# Sheet1.net
KiCad netlist of a schematic drawn in Altium Designer
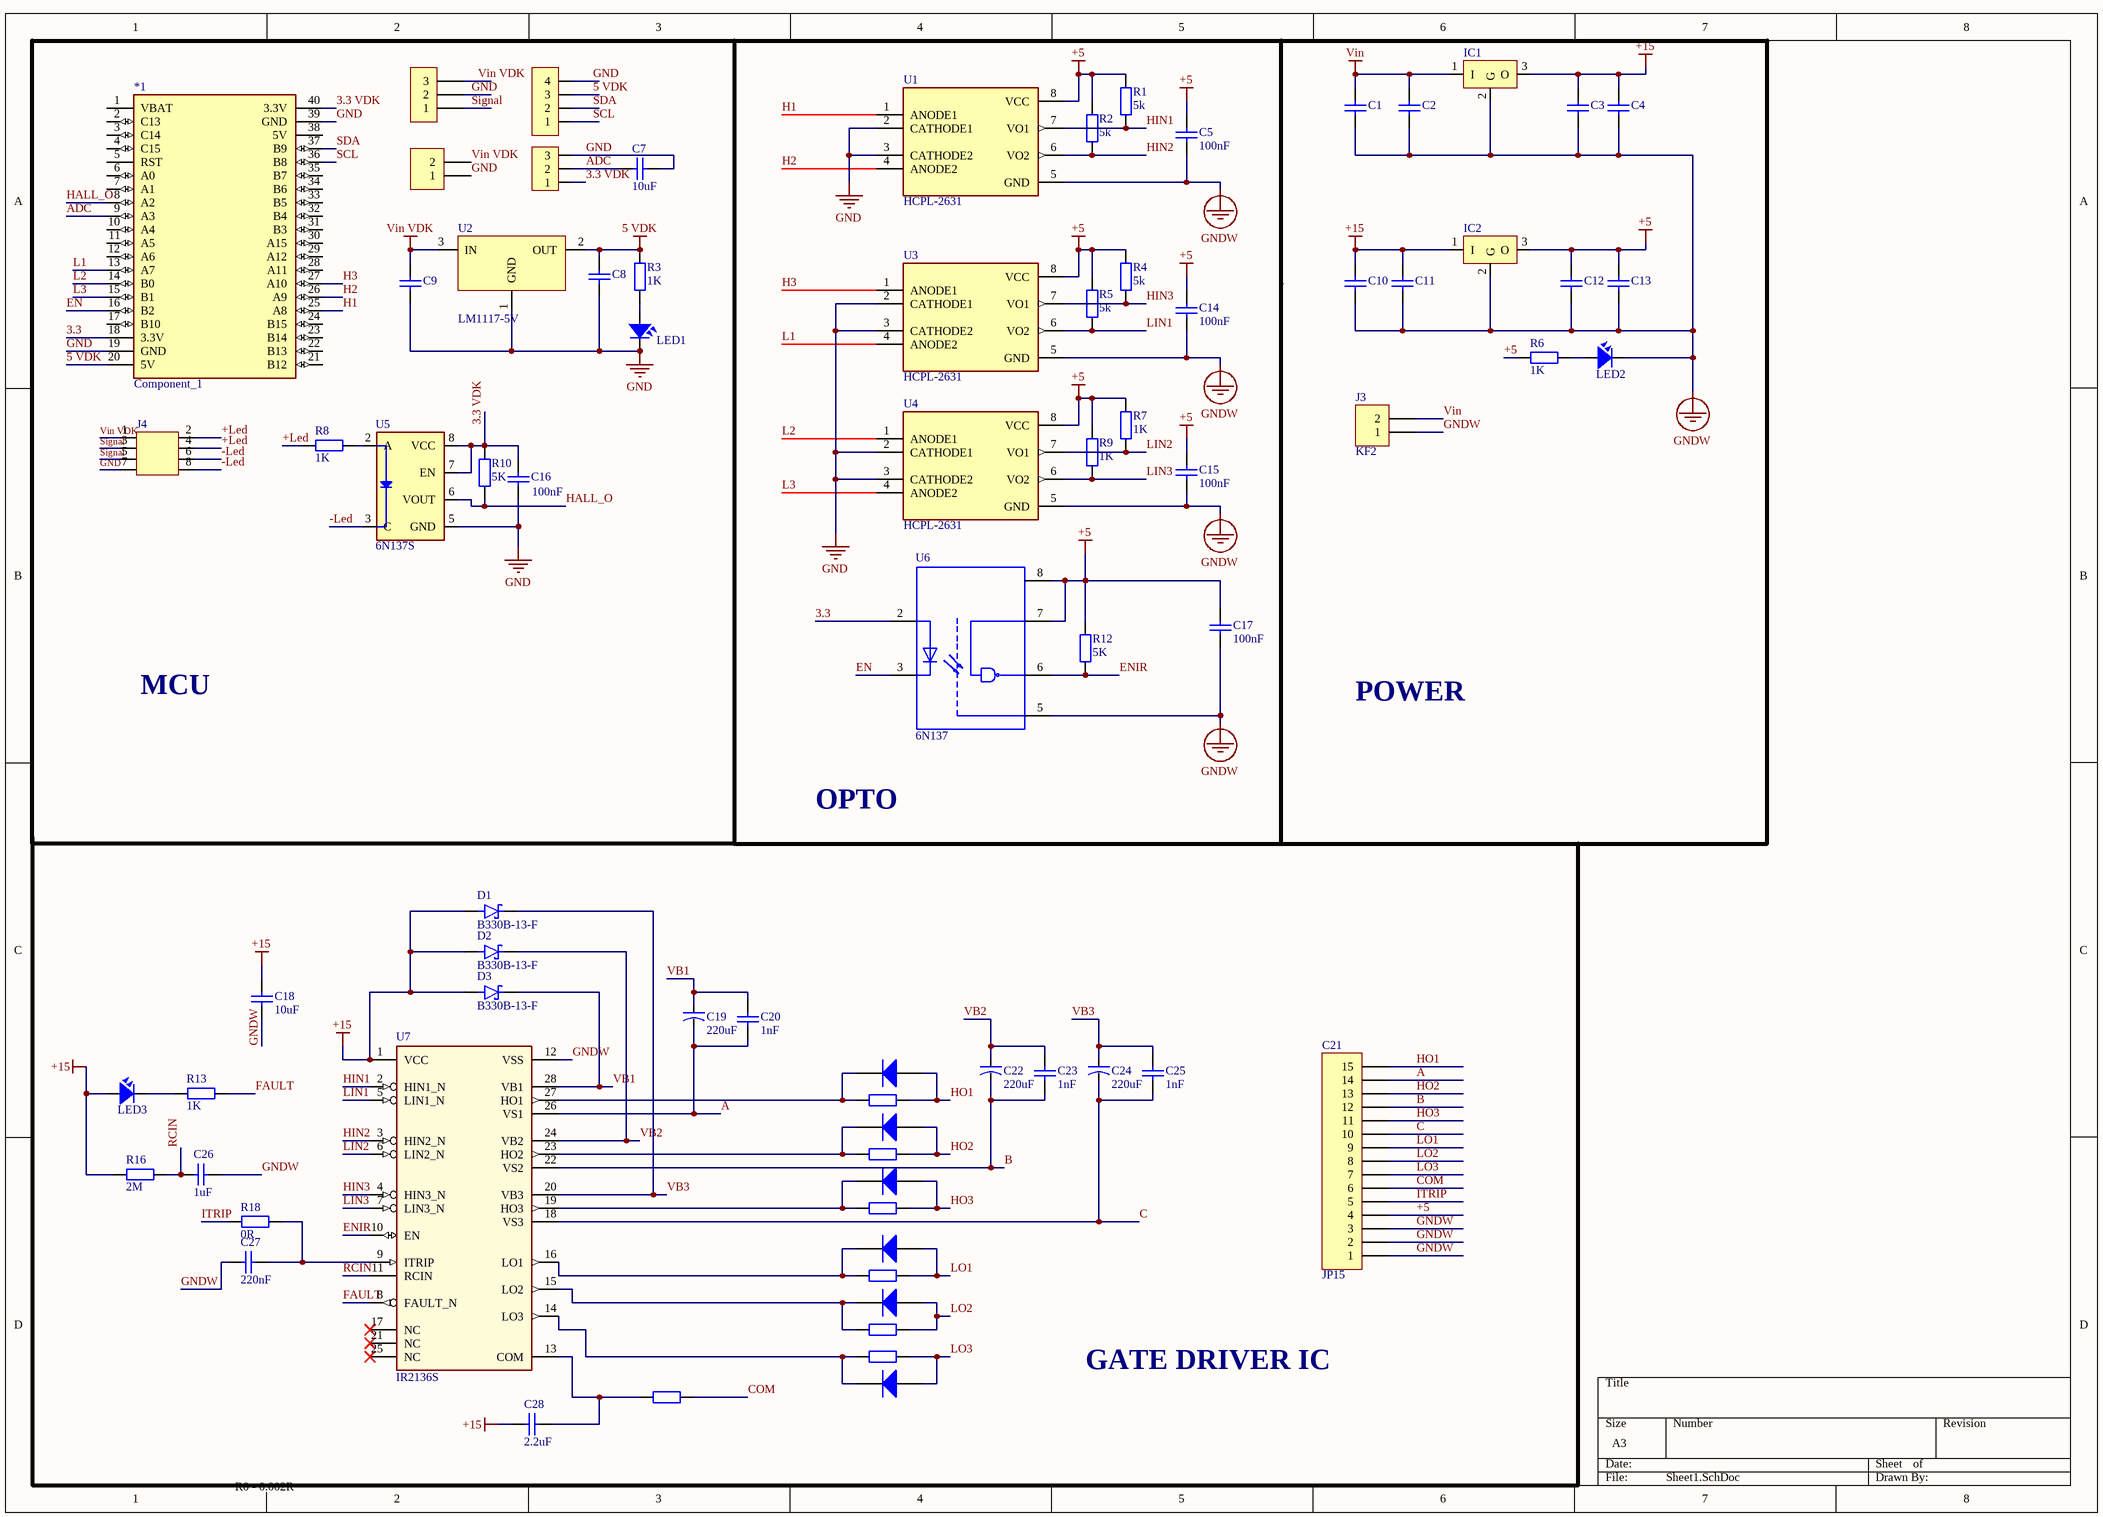
[diagram p0: Sheet1.SchDoc]

(export (version "E")
  (design (tool "Eeschema 10.0.6"))
  (components
    (comp (ref "*1")
      (value "Component_1")
      (footprint "PCBComponent_1")
      (libsource (lib "F401_black") (part "Component_1"))
    )
    (comp (ref "C1")
      (value "106")
      (footprint "tu 1206")
      (description "Dán")
      (libsource (lib "Altium_Lib_by_KhueNguyenCreator") (part "Tu 1206 106 16V 20%"))
    )
    (comp (ref "C2")
      (value "106")
      (footprint "tu 1206")
      (description "Dán")
      (libsource (lib "Altium_Lib_by_KhueNguyenCreator") (part "Tu 1206 106 16V 20%"))
    )
    (comp (ref "C3")
      (value "106")
      (footprint "tu 1206")
      (description "Dán")
      (libsource (lib "Altium_Lib_by_KhueNguyenCreator") (part "Tu 1206 106 16V 20%"))
    )
    (comp (ref "C4")
      (value "106")
      (footprint "tu 1206")
      (description "Dán")
      (libsource (lib "Altium_Lib_by_KhueNguyenCreator") (part "Tu 1206 106 16V 20%"))
    )
    (comp (ref "C5")
      (value "100nF")
      (footprint "tu 1206")
      (description "Dán")
      (libsource (lib "Altium_Lib_by_KhueNguyenCreator") (part "Tu 1206 470pF 50V 10%"))
    )
    (comp (ref "C6")
      (value "Header3")
      (footprint "Header3")
      (description "Header IDC, 3 x 1 Pin Vertical 2.54mm Pitch (Non-Boxed, Male)")
      (fields
        (field (name "MANUFACTURER") "Würth Elektronik eiSos GmbH")
        (field (name "PARTNO") "613002143121")
        (field (name "CREATED BY") "Karrer Zheng")
      )
      (libsource (lib "TechMT.VN_Lib_Project v2") (part "Header3"))
    )
    (comp (ref "C7")
      (value "10uF")
      (footprint "tu 1206")
      (description "Dán")
      (libsource (lib "Altium_Lib_by_KhueNguyenCreator") (part "Tu 1206 470pF 50V 10%"))
    )
    (comp (ref "C8")
      (value "106")
      (footprint "tu 1206")
      (description "Dán")
      (libsource (lib "Altium_Lib_by_KhueNguyenCreator") (part "Tu 1206 106 16V 20%"))
    )
    (comp (ref "C9")
      (value "106")
      (footprint "tu 1206")
      (description "Dán")
      (libsource (lib "Altium_Lib_by_KhueNguyenCreator") (part "Tu 1206 106 16V 20%"))
    )
    (comp (ref "C10")
      (value "106")
      (footprint "tu 1206")
      (description "Dán")
      (libsource (lib "Altium_Lib_by_KhueNguyenCreator") (part "Tu 1206 106 16V 20%"))
    )
    (comp (ref "C11")
      (value "106")
      (footprint "tu 1206")
      (description "Dán")
      (libsource (lib "Altium_Lib_by_KhueNguyenCreator") (part "Tu 1206 106 16V 20%"))
    )
    (comp (ref "C12")
      (value "106")
      (footprint "tu 1206")
      (description "Dán")
      (libsource (lib "Altium_Lib_by_KhueNguyenCreator") (part "Tu 1206 106 16V 20%"))
    )
    (comp (ref "C13")
      (value "106")
      (footprint "tu 1206")
      (description "Dán")
      (libsource (lib "Altium_Lib_by_KhueNguyenCreator") (part "Tu 1206 106 16V 20%"))
    )
    (comp (ref "C14")
      (value "100nF")
      (footprint "tu 1206")
      (description "Dán")
      (libsource (lib "Altium_Lib_by_KhueNguyenCreator") (part "Tu 1206 470pF 50V 10%"))
    )
    (comp (ref "C15")
      (value "100nF")
      (footprint "tu 1206")
      (description "Dán")
      (libsource (lib "Altium_Lib_by_KhueNguyenCreator") (part "Tu 1206 470pF 50V 10%"))
    )
    (comp (ref "C16")
      (value "100nF")
      (footprint "tu 1206")
      (description "Dán")
      (libsource (lib "Altium_Lib_by_KhueNguyenCreator") (part "Tu 1206 470pF 50V 10%"))
    )
    (comp (ref "C17")
      (value "100nF")
      (footprint "tu 1206")
      (description "Dán")
      (libsource (lib "Altium_Lib_by_KhueNguyenCreator") (part "Tu 1206 470pF 50V 10%"))
    )
    (comp (ref "C18")
      (value "10uF")
      (footprint "tu 1206")
      (description "Dán")
      (libsource (lib "Altium_Lib_by_KhueNguyenCreator") (part "Tu 1206 470pF 50V 10%"))
    )
    (comp (ref "C19")
      (value "220uF")
      (footprint "CA-ALU-8")
      (description "Capacitor (Semiconductor SIM Model)")
      (fields (field (name "PUBLISHER") "Altium Limited"))
      (libsource (lib "TechMT.VN_Lib_Project v2") (part "CN-ALU-DIP"))
    )
    (comp (ref "C20")
      (value "1nF")
      (footprint "tu 0805")
      (description "Dán")
      (libsource (lib "Altium_Lib_by_KhueNguyenCreator") (part "Tu 0805 20pF 50V 10%"))
    )
    (comp (ref "C21")
      (value "JP15")
      (footprint "JP15-D1T")
      (description "WR-PHD 2.54 mm Angled Socket Header")
      (fields
        (field (name "MANUFACTURER") "Würth Elektronik eiSos GmbH")
        (field (name "PARTNO") "613015143121")
        (field (name "CREATED BY") "Karrer Zheng")
      )
      (libsource (lib "TechMT.VN_Lib_Project v2") (part "JP15"))
    )
    (comp (ref "C22")
      (value "220uF")
      (footprint "CA-ALU-8")
      (description "Capacitor (Semiconductor SIM Model)")
      (fields (field (name "PUBLISHER") "Altium Limited"))
      (libsource (lib "TechMT.VN_Lib_Project v2") (part "CN-ALU-DIP"))
    )
    (comp (ref "C23")
      (value "1nF")
      (footprint "tu 0805")
      (description "Dán")
      (libsource (lib "Altium_Lib_by_KhueNguyenCreator") (part "Tu 0805 20pF 50V 10%"))
    )
    (comp (ref "C24")
      (value "220uF")
      (footprint "CA-ALU-8")
      (description "Capacitor (Semiconductor SIM Model)")
      (fields (field (name "PUBLISHER") "Altium Limited"))
      (libsource (lib "TechMT.VN_Lib_Project v2") (part "CN-ALU-DIP"))
    )
    (comp (ref "C25")
      (value "1nF")
      (footprint "tu 0805")
      (description "Dán")
      (libsource (lib "Altium_Lib_by_KhueNguyenCreator") (part "Tu 0805 20pF 50V 10%"))
    )
    (comp (ref "C26")
      (value "1uF")
      (footprint "tu 1206")
      (description "Dán")
      (libsource (lib "Altium_Lib_by_KhueNguyenCreator") (part "Tu 1206 470pF 50V 10%"))
    )
    (comp (ref "C27")
      (value "220nF")
      (footprint "tu 1206")
      (description "Dán")
      (libsource (lib "Altium_Lib_by_KhueNguyenCreator") (part "Tu 1206 470pF 50V 10%"))
    )
    (comp (ref "C28")
      (value "2.2uF")
      (footprint "tu 1206")
      (description "Dán")
      (libsource (lib "Altium_Lib_by_KhueNguyenCreator") (part "Tu 1206 470pF 50V 10%"))
    )
    (comp (ref "D1")
      (value "B330B-13-F")
      (footprint "DIOM5336X240N")
      (description "Diode Schottky 30 V 3A Surface Mount SMB")
      (fields (field (name "MF") "Diodes Inc."))
      (libsource (lib "Do214AA_SMB_Diode") (part "B330B-13-F"))
    )
    (comp (ref "D2")
      (value "B330B-13-F")
      (footprint "DIOM5336X240N")
      (description "Diode Schottky 30 V 3A Surface Mount SMB")
      (fields (field (name "MF") "Diodes Inc."))
      (libsource (lib "Do214AA_SMB_Diode") (part "B330B-13-F"))
    )
    (comp (ref "D3")
      (value "B330B-13-F")
      (footprint "DIOM5336X240N")
      (description "Diode Schottky 30 V 3A Surface Mount SMB")
      (fields (field (name "MF") "Diodes Inc."))
      (libsource (lib "Do214AA_SMB_Diode") (part "B330B-13-F"))
    )
    (comp (ref "D4")
      (value "SS14")
      (footprint "DIODE SMA")
      (description "Dán")
      (libsource (lib "Altium_Lib_by_KhueNguyenCreator") (part "Diode SS14 ( 1N5819)"))
    )
    (comp (ref "D5")
      (value "SS14")
      (footprint "DIODE SMA")
      (description "Dán")
      (libsource (lib "Altium_Lib_by_KhueNguyenCreator") (part "Diode SS14 ( 1N5819)"))
    )
    (comp (ref "D6")
      (value "SS14")
      (footprint "DIODE SMA")
      (description "Dán")
      (libsource (lib "Altium_Lib_by_KhueNguyenCreator") (part "Diode SS14 ( 1N5819)"))
    )
    (comp (ref "D7")
      (value "SS14")
      (footprint "DIODE SMA")
      (description "Dán")
      (libsource (lib "Altium_Lib_by_KhueNguyenCreator") (part "Diode SS14 ( 1N5819)"))
    )
    (comp (ref "D8")
      (value "SS14")
      (footprint "DIODE SMA")
      (description "Dán")
      (libsource (lib "Altium_Lib_by_KhueNguyenCreator") (part "Diode SS14 ( 1N5819)"))
    )
    (comp (ref "D9")
      (value "SS14")
      (footprint "DIODE SMA")
      (description "Dán")
      (libsource (lib "Altium_Lib_by_KhueNguyenCreator") (part "Diode SS14 ( 1N5819)"))
    )
    (comp (ref "IC1")
      (value "LM78xx")
      (footprint "TO220-123")
      (description "Positive Voltage Regulator")
      (fields (field (name "PUBLISHER") "Altium Limited"))
      (libsource (lib "TechMT.VN_Lib_Project v2") (part "LM78xx"))
    )
    (comp (ref "IC2")
      (value "LM78xx")
      (footprint "TO220-123")
      (description "Positive Voltage Regulator")
      (fields (field (name "PUBLISHER") "Altium Limited"))
      (libsource (lib "TechMT.VN_Lib_Project v2") (part "LM78xx"))
    )
    (comp (ref "J1")
      (value "KF3")
      (footprint "KF3-5.08T")
      (fields
        (field (name "MANUFACTURER") "Würth Elektronik eiSos GmbH")
        (field (name "PARTNO") "691103110003")
        (field (name "CREATED BY") "Karrer Zheng")
      )
      (libsource (lib "TechMT.VN_Lib_Project v2") (part "KF3"))
    )
    (comp (ref "J2")
      (value "KF2")
      (footprint "KF2-5.08T")
      (fields
        (field (name "MANUFACTURER") "Würth Elektronik eiSos GmbH")
        (field (name "PARTNO") "691103110002")
        (field (name "CREATED BY") "Karrer Zheng")
      )
      (libsource (lib "TechMT.VN_Lib_Project v2") (part "KF2"))
    )
    (comp (ref "J3")
      (value "KF2")
      (footprint "KF2-5.08T")
      (fields
        (field (name "MANUFACTURER") "Würth Elektronik eiSos GmbH")
        (field (name "PARTNO") "691103110002")
        (field (name "CREATED BY") "Karrer Zheng")
      )
      (libsource (lib "TechMT.VN_Lib_Project v2") (part "KF2"))
    )
    (comp (ref "J4")
      (value "SAMTEC-TSM-102-01-X-DV")
      (footprint "SAMTEC-TSM-102-01-X-DV")
      (description "TSM Series .100 Surface Mount Terminal Strip")
      (fields (field (name "MF") "Samtec") (field (name "MP") "TSM-102-01-F-DV"))
      (libsource (lib "JP2x4 SMD") (part "SAMTEC-TSM-102-01-X-DV"))
    )
    (comp (ref "JP1")
      (value "JP 1x4 2.54")
      (footprint "JP 1x4 DC")
      (description "Cắm")
      (libsource (lib "Altium_Lib_by_KhueNguyenCreator") (part "JP 1x4 2.54 Duc Cong"))
    )
    (comp (ref "LED1")
      (value "LED")
      (footprint "LED-1206-Blue")
      (libsource (lib "TechMT.VN_Lib_Project v2") (part "LED SMD"))
    )
    (comp (ref "LED2")
      (value "LED")
      (footprint "LED-1206-Blue")
      (libsource (lib "TechMT.VN_Lib_Project v2") (part "LED SMD"))
    )
    (comp (ref "LED3")
      (value "LED")
      (footprint "LED-1206-Blue")
      (libsource (lib "TechMT.VN_Lib_Project v2") (part "LED SMD"))
    )
    (comp (ref "R1")
      (value "5k")
      (footprint "tro smd 1206")
      (description "Dán")
      (libsource (lib "Altium_Lib_by_KhueNguyenCreator") (part "Tro 1206 5% 680R"))
    )
    (comp (ref "R2")
      (value "5k")
      (footprint "tro smd 1206")
      (description "Dán")
      (libsource (lib "Altium_Lib_by_KhueNguyenCreator") (part "Tro 1206 5% 680R"))
    )
    (comp (ref "R3")
      (value "1K")
      (footprint "tro smd 1206")
      (description "Dán")
      (libsource (lib "Altium_Lib_by_KhueNguyenCreator") (part "Tro 1206 5% 680R"))
    )
    (comp (ref "R4")
      (value "5k")
      (footprint "tro smd 1206")
      (description "Dán")
      (libsource (lib "Altium_Lib_by_KhueNguyenCreator") (part "Tro 1206 5% 680R"))
    )
    (comp (ref "R5")
      (value "5k")
      (footprint "tro smd 1206")
      (description "Dán")
      (libsource (lib "Altium_Lib_by_KhueNguyenCreator") (part "Tro 1206 5% 680R"))
    )
    (comp (ref "R6")
      (value "1K")
      (footprint "tro smd 1206")
      (description "Dán")
      (libsource (lib "Altium_Lib_by_KhueNguyenCreator") (part "Tro 1206 5% 680R"))
    )
    (comp (ref "R7")
      (value "1K")
      (footprint "tro smd 1206")
      (description "Dán")
      (libsource (lib "Altium_Lib_by_KhueNguyenCreator") (part "Tro 1206 5% 680R"))
    )
    (comp (ref "R8")
      (value "1K")
      (footprint "tro smd 1206")
      (description "Dán")
      (libsource (lib "Altium_Lib_by_KhueNguyenCreator") (part "Tro 1206 5% 680R"))
    )
    (comp (ref "R9")
      (value "1K")
      (footprint "tro smd 1206")
      (description "Dán")
      (libsource (lib "Altium_Lib_by_KhueNguyenCreator") (part "Tro 1206 5% 680R"))
    )
    (comp (ref "R10")
      (value "5K")
      (footprint "tro smd 1206")
      (description "Dán")
      (libsource (lib "Altium_Lib_by_KhueNguyenCreator") (part "Tro 1206 5% 680R"))
    )
    (comp (ref "R12")
      (value "5K")
      (footprint "tro smd 1206")
      (description "Dán")
      (libsource (lib "Altium_Lib_by_KhueNguyenCreator") (part "Tro 1206 5% 680R"))
    )
    (comp (ref "R13")
      (value "1K")
      (footprint "tro smd 1206")
      (description "Dán")
      (libsource (lib "Altium_Lib_by_KhueNguyenCreator") (part "Tro 1206 5% 680R"))
    )
    (comp (ref "R14")
      (value "680R")
      (footprint "tro smd 1206")
      (description "Dán")
      (libsource (lib "Altium_Lib_by_KhueNguyenCreator") (part "Tro 1206 5% 680R"))
    )
    (comp (ref "R15")
      (value "680R")
      (footprint "tro smd 1206")
      (description "Dán")
      (libsource (lib "Altium_Lib_by_KhueNguyenCreator") (part "Tro 1206 5% 680R"))
    )
    (comp (ref "R16")
      (value "2M")
      (footprint "tro smd 1206")
      (description "Dán")
      (libsource (lib "Altium_Lib_by_KhueNguyenCreator") (part "Tro 1206 5% 680R"))
    )
    (comp (ref "R17")
      (value "680R")
      (footprint "tro smd 1206")
      (description "Dán")
      (libsource (lib "Altium_Lib_by_KhueNguyenCreator") (part "Tro 1206 5% 680R"))
    )
    (comp (ref "R18")
      (value "0R")
      (footprint "tro smd 1206")
      (description "Dán")
      (libsource (lib "Altium_Lib_by_KhueNguyenCreator") (part "Tro 1206 5% 680R"))
    )
    (comp (ref "R19")
      (value "680R")
      (footprint "tro smd 1206")
      (description "Dán")
      (libsource (lib "Altium_Lib_by_KhueNguyenCreator") (part "Tro 1206 5% 680R"))
    )
    (comp (ref "R20")
      (value "680R")
      (footprint "tro smd 1206")
      (description "Dán")
      (libsource (lib "Altium_Lib_by_KhueNguyenCreator") (part "Tro 1206 5% 680R"))
    )
    (comp (ref "R21")
      (value "680R")
      (footprint "tro smd 1206")
      (description "Dán")
      (libsource (lib "Altium_Lib_by_KhueNguyenCreator") (part "Tro 1206 5% 680R"))
    )
    (comp (ref "R22")
      (value "1R")
      (footprint "tro smd 1206")
      (description "Dán")
      (libsource (lib "Altium_Lib_by_KhueNguyenCreator") (part "Tro 1206 5% 680R"))
    )
    (comp (ref "U1")
      (value "HCPL-2631")
      (footprint "DIP762W65P254L965H470Q8")
      (fields (field (name "MF") "Broadcom Limited"))
      (libsource (lib "HCPL-2631") (part "HCPL-2631"))
    )
    (comp (ref "U2")
      (value "LM1117-5V")
      (footprint "SOT223")
      (description "800mA Low-Dropout Linear Regulator")
      (fields (field (name "CREATOR") "Nguyen Ba Bien"))
      (libsource (lib "TechMT.VN_Lib_Project v2") (part "LM1117"))
    )
    (comp (ref "U3")
      (value "HCPL-2631")
      (footprint "DIP762W65P254L965H470Q8")
      (fields (field (name "MF") "Broadcom Limited"))
      (libsource (lib "HCPL-2631") (part "HCPL-2631"))
    )
    (comp (ref "U4")
      (value "HCPL-2631")
      (footprint "DIP762W65P254L965H470Q8")
      (fields (field (name "MF") "Broadcom Limited"))
      (libsource (lib "HCPL-2631") (part "HCPL-2631"))
    )
    (comp (ref "U5")
      (value "6N137S")
      (footprint "8-SMD")
      (description "Logic Output Optoisolator 15MBd Open Collector 5000Vrms 1 Channel 10kV/Âµs CMTI 8-SMD")
      (fields (field (name "MF") "Lite-On Inc."))
      (libsource (lib "6N137S") (part "6N137S"))
    )
    (comp (ref "U6")
      (value "6N137")
      (footprint "DIP762W50P254L977H451Q8")
      (description "Optoaislador de salida lÃ³gica 10Mbps Open Collector 5000Vrms 1 Channel 5kV / Âµs CMTI 8-DIP")
      (fields (field (name "MF") "Everlight Electronics"))
      (libsource (lib "6N137") (part "6N137"))
    )
    (comp (ref "U7")
      (value "IR2136S")
      (footprint "SOIC127P1032X265-28N")
      (description "High Voltage Gate Driver IC")
      (fields (field (name "MANUFACTURER") "Infineon Technologies"))
      (libsource (lib "IR2136") (part "IR2136S"))
    )
  )
  (nets
    (net (code "1") (name "+5") (class "Default")
      (node (ref "C12") (pin "1") (pinfunction "1_1") (pintype "passive"))
      (node (ref "C13") (pin "1") (pinfunction "1_1") (pintype "passive"))
      (node (ref "C14") (pin "2") (pinfunction "2_2") (pintype "passive"))
      (node (ref "C15") (pin "2") (pinfunction "2_2") (pintype "passive"))
      (node (ref "C17") (pin "2") (pinfunction "2_2") (pintype "passive"))
      (node (ref "C21") (pin "4") (pinfunction "4_4") (pintype "passive"))
      (node (ref "C5") (pin "2") (pinfunction "2_2") (pintype "passive"))
      (node (ref "IC2") (pin "3") (pinfunction "O_3") (pintype "power_in"))
      (node (ref "R1") (pin "2") (pinfunction "2_2") (pintype "passive"))
      (node (ref "R12") (pin "2") (pinfunction "2_2") (pintype "passive"))
      (node (ref "R2") (pin "2") (pinfunction "2_2") (pintype "passive"))
      (node (ref "R4") (pin "2") (pinfunction "2_2") (pintype "passive"))
      (node (ref "R5") (pin "2") (pinfunction "2_2") (pintype "passive"))
      (node (ref "R6") (pin "1") (pinfunction "1_1") (pintype "passive"))
      (node (ref "R7") (pin "2") (pinfunction "2_2") (pintype "passive"))
      (node (ref "R9") (pin "2") (pinfunction "2_2") (pintype "passive"))
      (node (ref "U1") (pin "8") (pinfunction "VCC_8") (pintype "power_in"))
      (node (ref "U3") (pin "8") (pinfunction "VCC_8") (pintype "power_in"))
      (node (ref "U4") (pin "8") (pinfunction "VCC_8") (pintype "power_in"))
      (node (ref "U6") (pin "7") (pinfunction "VE_7") (pintype "passive"))
      (node (ref "U6") (pin "8") (pinfunction "VCC_8") (pintype "power_in"))
    )
    (net (code "2") (name "+15") (class "Default")
      (node (ref "C10") (pin "1") (pinfunction "1_1") (pintype "passive"))
      (node (ref "C11") (pin "1") (pinfunction "1_1") (pintype "passive"))
      (node (ref "C18") (pin "2") (pinfunction "2_2") (pintype "passive"))
      (node (ref "C28") (pin "2") (pinfunction "2_2") (pintype "passive"))
      (node (ref "C3") (pin "1") (pinfunction "1_1") (pintype "passive"))
      (node (ref "C4") (pin "1") (pinfunction "1_1") (pintype "passive"))
      (node (ref "D1") (pin "A") (pinfunction "A_A") (pintype "passive"))
      (node (ref "D2") (pin "A") (pinfunction "A_A") (pintype "passive"))
      (node (ref "D3") (pin "A") (pinfunction "A_A") (pintype "passive"))
      (node (ref "IC1") (pin "3") (pinfunction "O_3") (pintype "power_in"))
      (node (ref "IC2") (pin "1") (pinfunction "I_1") (pintype "power_in"))
      (node (ref "LED3") (pin "1") (pinfunction "1_1") (pintype "passive"))
      (node (ref "R16") (pin "2") (pinfunction "2_2") (pintype "passive"))
      (node (ref "U7") (pin "1") (pinfunction "VCC_1") (pintype "power_in"))
    )
    (net (code "3") (name "/+Led") (class "Default")
      (node (ref "J4") (pin "2") (pinfunction "2_2") (pintype "passive"))
      (node (ref "J4") (pin "4") (pinfunction "4_4") (pintype "passive"))
      (node (ref "R8") (pin "2") (pinfunction "2_2") (pintype "passive"))
    )
    (net (code "4") (name "/-Led") (class "Default")
      (node (ref "J4") (pin "6") (pinfunction "6_6") (pintype "passive"))
      (node (ref "J4") (pin "8") (pinfunction "8_8") (pintype "passive"))
      (node (ref "U5") (pin "3") (pinfunction "C_3") (pintype "bidirectional"))
    )
    (net (code "5") (name "/3.3") (class "Default")
      (node (ref "*1") (pin "18") (pinfunction "3.3V_18") (pintype "power_in"))
      (node (ref "U6") (pin "2") (pinfunction "A_2") (pintype "passive"))
    )
    (net (code "6") (name "/3.3 VDK") (class "Default")
      (node (ref "*1") (pin "40") (pinfunction "3.3V_40") (pintype "power_in"))
      (node (ref "C16") (pin "2") (pinfunction "2_2") (pintype "passive"))
      (node (ref "C6") (pin "1") (pinfunction "1_1") (pintype "passive"))
      (node (ref "R10") (pin "2") (pinfunction "2_2") (pintype "passive"))
      (node (ref "U5") (pin "7") (pinfunction "EN_7") (pintype "bidirectional"))
      (node (ref "U5") (pin "8") (pinfunction "VCC_8") (pintype "bidirectional"))
    )
    (net (code "7") (name "/A") (class "Default")
      (node (ref "C19") (pin "2") (pinfunction "2_2") (pintype "passive"))
      (node (ref "C20") (pin "2") (pinfunction "2_2") (pintype "passive"))
      (node (ref "C21") (pin "14") (pinfunction "14_14") (pintype "passive"))
      (node (ref "U7") (pin "26") (pinfunction "VS1_26") (pintype "power_in"))
    )
    (net (code "8") (name "/ADC") (class "Default")
      (node (ref "*1") (pin "9") (pinfunction "A3_9") (pintype "bidirectional"))
      (node (ref "C6") (pin "2") (pinfunction "2_2") (pintype "passive"))
      (node (ref "C7") (pin "2") (pinfunction "2_2") (pintype "passive"))
    )
    (net (code "9") (name "/B") (class "Default")
      (node (ref "C21") (pin "12") (pinfunction "12_12") (pintype "passive"))
      (node (ref "C22") (pin "2") (pinfunction "2_2") (pintype "passive"))
      (node (ref "C23") (pin "2") (pinfunction "2_2") (pintype "passive"))
      (node (ref "U7") (pin "22") (pinfunction "VS2_22") (pintype "power_in"))
    )
    (net (code "10") (name "/C") (class "Default")
      (node (ref "C21") (pin "10") (pinfunction "10_10") (pintype "passive"))
      (node (ref "C24") (pin "2") (pinfunction "2_2") (pintype "passive"))
      (node (ref "C25") (pin "2") (pinfunction "2_2") (pintype "passive"))
      (node (ref "U7") (pin "18") (pinfunction "VS3_18") (pintype "power_in"))
    )
    (net (code "11") (name "/COM") (class "Default")
      (node (ref "C21") (pin "6") (pinfunction "6_6") (pintype "passive"))
      (node (ref "R22") (pin "1") (pinfunction "1_1") (pintype "passive"))
    )
    (net (code "12") (name "/EN") (class "Default")
      (node (ref "*1") (pin "16") (pinfunction "B2_16") (pintype "bidirectional"))
      (node (ref "U6") (pin "3") (pinfunction "C_3") (pintype "passive"))
    )
    (net (code "13") (name "/ENIR") (class "Default")
      (node (ref "R12") (pin "1") (pinfunction "1_1") (pintype "passive"))
      (node (ref "U6") (pin "6") (pinfunction "VO_6") (pintype "passive"))
      (node (ref "U7") (pin "10") (pinfunction "EN_10") (pintype "bidirectional"))
    )
    (net (code "14") (name "/FAULT") (class "Default")
      (node (ref "R13") (pin "2") (pinfunction "2_2") (pintype "passive"))
      (node (ref "U7") (pin "8") (pinfunction "FAULT_N_8") (pintype "output"))
    )
    (net (code "15") (name "/H1") (class "Default")
      (node (ref "*1") (pin "25") (pinfunction "A8_25") (pintype "bidirectional"))
      (node (ref "U1") (pin "1") (pinfunction "ANODE1_1") (pintype "passive"))
    )
    (net (code "16") (name "/H2") (class "Default")
      (node (ref "*1") (pin "26") (pinfunction "A9_26") (pintype "bidirectional"))
      (node (ref "U1") (pin "4") (pinfunction "ANODE2_4") (pintype "passive"))
    )
    (net (code "17") (name "/H3") (class "Default")
      (node (ref "*1") (pin "27") (pinfunction "A10_27") (pintype "bidirectional"))
      (node (ref "U3") (pin "1") (pinfunction "ANODE1_1") (pintype "passive"))
    )
    (net (code "18") (name "/HALL_O") (class "Default")
      (node (ref "*1") (pin "8") (pinfunction "A2_8") (pintype "bidirectional"))
      (node (ref "R10") (pin "1") (pinfunction "1_1") (pintype "passive"))
      (node (ref "U5") (pin "6") (pinfunction "VOUT_6") (pintype "bidirectional"))
    )
    (net (code "19") (name "/HIN1") (class "Default")
      (node (ref "R1") (pin "1") (pinfunction "1_1") (pintype "passive"))
      (node (ref "U1") (pin "7") (pinfunction "VO1_7") (pintype "output"))
      (node (ref "U7") (pin "2") (pinfunction "HIN1_N_2") (pintype "input"))
    )
    (net (code "20") (name "/HIN2") (class "Default")
      (node (ref "R2") (pin "1") (pinfunction "1_1") (pintype "passive"))
      (node (ref "U1") (pin "6") (pinfunction "VO2_6") (pintype "output"))
      (node (ref "U7") (pin "3") (pinfunction "HIN2_N_3") (pintype "input"))
    )
    (net (code "21") (name "/HIN3") (class "Default")
      (node (ref "R4") (pin "1") (pinfunction "1_1") (pintype "passive"))
      (node (ref "U3") (pin "7") (pinfunction "VO1_7") (pintype "output"))
      (node (ref "U7") (pin "4") (pinfunction "HIN3_N_4") (pintype "input"))
    )
    (net (code "22") (name "/HO1") (class "Default")
      (node (ref "C21") (pin "15") (pinfunction "15_15") (pintype "passive"))
      (node (ref "D4") (pin "1") (pinfunction "A_1") (pintype "passive"))
      (node (ref "R14") (pin "1") (pinfunction "1_1") (pintype "passive"))
    )
    (net (code "23") (name "/HO2") (class "Default")
      (node (ref "C21") (pin "13") (pinfunction "13_13") (pintype "passive"))
      (node (ref "D5") (pin "1") (pinfunction "A_1") (pintype "passive"))
      (node (ref "R15") (pin "1") (pinfunction "1_1") (pintype "passive"))
    )
    (net (code "24") (name "/HO3") (class "Default")
      (node (ref "C21") (pin "11") (pinfunction "11_11") (pintype "passive"))
      (node (ref "D6") (pin "1") (pinfunction "A_1") (pintype "passive"))
      (node (ref "R17") (pin "1") (pinfunction "1_1") (pintype "passive"))
    )
    (net (code "25") (name "/ITRIP") (class "Default")
      (node (ref "C21") (pin "5") (pinfunction "5_5") (pintype "passive"))
      (node (ref "R18") (pin "1") (pinfunction "1_1") (pintype "passive"))
    )
    (net (code "26") (name "/L1") (class "Default")
      (node (ref "*1") (pin "13") (pinfunction "A7_13") (pintype "bidirectional"))
      (node (ref "U3") (pin "4") (pinfunction "ANODE2_4") (pintype "passive"))
    )
    (net (code "27") (name "/L2") (class "Default")
      (node (ref "*1") (pin "14") (pinfunction "B0_14") (pintype "bidirectional"))
      (node (ref "U4") (pin "1") (pinfunction "ANODE1_1") (pintype "passive"))
    )
    (net (code "28") (name "/L3") (class "Default")
      (node (ref "*1") (pin "15") (pinfunction "B1_15") (pintype "bidirectional"))
      (node (ref "U4") (pin "4") (pinfunction "ANODE2_4") (pintype "passive"))
    )
    (net (code "29") (name "/LIN1") (class "Default")
      (node (ref "R5") (pin "1") (pinfunction "1_1") (pintype "passive"))
      (node (ref "U3") (pin "6") (pinfunction "VO2_6") (pintype "output"))
      (node (ref "U7") (pin "5") (pinfunction "LIN1_N_5") (pintype "input"))
    )
    (net (code "30") (name "/LIN2") (class "Default")
      (node (ref "R7") (pin "1") (pinfunction "1_1") (pintype "passive"))
      (node (ref "U4") (pin "7") (pinfunction "VO1_7") (pintype "output"))
      (node (ref "U7") (pin "6") (pinfunction "LIN2_N_6") (pintype "input"))
    )
    (net (code "31") (name "/LIN3") (class "Default")
      (node (ref "R9") (pin "1") (pinfunction "1_1") (pintype "passive"))
      (node (ref "U4") (pin "6") (pinfunction "VO2_6") (pintype "output"))
      (node (ref "U7") (pin "7") (pinfunction "LIN3_N_7") (pintype "input"))
    )
    (net (code "32") (name "/LO1") (class "Default")
      (node (ref "C21") (pin "9") (pinfunction "9_9") (pintype "passive"))
      (node (ref "D7") (pin "1") (pinfunction "A_1") (pintype "passive"))
      (node (ref "R19") (pin "1") (pinfunction "1_1") (pintype "passive"))
    )
    (net (code "33") (name "/LO2") (class "Default")
      (node (ref "C21") (pin "8") (pinfunction "8_8") (pintype "passive"))
      (node (ref "D8") (pin "1") (pinfunction "A_1") (pintype "passive"))
      (node (ref "R20") (pin "1") (pinfunction "1_1") (pintype "passive"))
    )
    (net (code "34") (name "/LO3") (class "Default")
      (node (ref "C21") (pin "7") (pinfunction "7_7") (pintype "passive"))
      (node (ref "D9") (pin "1") (pinfunction "A_1") (pintype "passive"))
      (node (ref "R21") (pin "1") (pinfunction "1_1") (pintype "passive"))
    )
    (net (code "35") (name "/RCIN") (class "Default")
      (node (ref "C26") (pin "1") (pinfunction "1_1") (pintype "passive"))
      (node (ref "R16") (pin "1") (pinfunction "1_1") (pintype "passive"))
      (node (ref "U7") (pin "11") (pinfunction "RCIN_11") (pintype "passive"))
    )
    (net (code "36") (name "/SCL") (class "Default")
      (node (ref "*1") (pin "36") (pinfunction "B8_36") (pintype "bidirectional"))
      (node (ref "JP1") (pin "1") (pinfunction "1_1") (pintype "passive"))
    )
    (net (code "37") (name "/SDA") (class "Default")
      (node (ref "*1") (pin "37") (pinfunction "B9_37") (pintype "bidirectional"))
      (node (ref "JP1") (pin "2") (pinfunction "2_2") (pintype "passive"))
    )
    (net (code "38") (name "/Signal") (class "Default")
      (node (ref "J1") (pin "1") (pinfunction "1_1") (pintype "passive"))
      (node (ref "J4") (pin "3") (pinfunction "3_3") (pintype "passive"))
      (node (ref "J4") (pin "5") (pinfunction "5_5") (pintype "passive"))
    )
    (net (code "39") (name "/VB1") (class "Default")
      (node (ref "C19") (pin "1") (pinfunction "1_1") (pintype "passive"))
      (node (ref "C20") (pin "1") (pinfunction "1_1") (pintype "passive"))
      (node (ref "D3") (pin "C") (pinfunction "K_C") (pintype "passive"))
      (node (ref "U7") (pin "28") (pinfunction "VB1_28") (pintype "power_in"))
    )
    (net (code "40") (name "/VB2") (class "Default")
      (node (ref "C22") (pin "1") (pinfunction "1_1") (pintype "passive"))
      (node (ref "C23") (pin "1") (pinfunction "1_1") (pintype "passive"))
      (node (ref "D2") (pin "C") (pinfunction "K_C") (pintype "passive"))
      (node (ref "U7") (pin "24") (pinfunction "VB2_24") (pintype "power_in"))
    )
    (net (code "41") (name "/VB3") (class "Default")
      (node (ref "C24") (pin "1") (pinfunction "1_1") (pintype "passive"))
      (node (ref "C25") (pin "1") (pinfunction "1_1") (pintype "passive"))
      (node (ref "D1") (pin "C") (pinfunction "K_C") (pintype "passive"))
      (node (ref "U7") (pin "20") (pinfunction "VB3_20") (pintype "power_in"))
    )
    (net (code "42") (name "5 VDK") (class "Default")
      (node (ref "*1") (pin "20") (pinfunction "5V_20") (pintype "power_in"))
      (node (ref "C8") (pin "1") (pinfunction "1_1") (pintype "passive"))
      (node (ref "JP1") (pin "3") (pinfunction "3_3") (pintype "passive"))
      (node (ref "R3") (pin "1") (pinfunction "1_1") (pintype "passive"))
      (node (ref "U2") (pin "2") (pinfunction "OUT_2") (pintype "passive"))
    )
    (net (code "43") (name "GND") (class "Default")
      (node (ref "*1") (pin "19") (pinfunction "GND_19") (pintype "power_in"))
      (node (ref "*1") (pin "39") (pinfunction "GND_39") (pintype "power_in"))
      (node (ref "C16") (pin "1") (pinfunction "1_1") (pintype "passive"))
      (node (ref "C6") (pin "3") (pinfunction "3_3") (pintype "passive"))
      (node (ref "C7") (pin "1") (pinfunction "1_1") (pintype "passive"))
      (node (ref "C8") (pin "2") (pinfunction "2_2") (pintype "passive"))
      (node (ref "C9") (pin "2") (pinfunction "2_2") (pintype "passive"))
      (node (ref "J1") (pin "2") (pinfunction "2_2") (pintype "passive"))
      (node (ref "J2") (pin "1") (pinfunction "1_1") (pintype "passive"))
      (node (ref "J4") (pin "7") (pinfunction "7_7") (pintype "passive"))
      (node (ref "JP1") (pin "4") (pinfunction "4_4") (pintype "passive"))
      (node (ref "LED1") (pin "2") (pinfunction "2_2") (pintype "passive"))
      (node (ref "U1") (pin "2") (pinfunction "CATHODE1_2") (pintype "passive"))
      (node (ref "U1") (pin "3") (pinfunction "CATHODE2_3") (pintype "passive"))
      (node (ref "U2") (pin "1") (pinfunction "GND_1") (pintype "passive"))
      (node (ref "U3") (pin "2") (pinfunction "CATHODE1_2") (pintype "passive"))
      (node (ref "U3") (pin "3") (pinfunction "CATHODE2_3") (pintype "passive"))
      (node (ref "U4") (pin "2") (pinfunction "CATHODE1_2") (pintype "passive"))
      (node (ref "U4") (pin "3") (pinfunction "CATHODE2_3") (pintype "passive"))
      (node (ref "U5") (pin "5") (pinfunction "GND_5") (pintype "bidirectional"))
    )
    (net (code "44") (name "GNDW") (class "Default")
      (node (ref "C1") (pin "2") (pinfunction "2_2") (pintype "passive"))
      (node (ref "C10") (pin "2") (pinfunction "2_2") (pintype "passive"))
      (node (ref "C11") (pin "2") (pinfunction "2_2") (pintype "passive"))
      (node (ref "C12") (pin "2") (pinfunction "2_2") (pintype "passive"))
      (node (ref "C13") (pin "2") (pinfunction "2_2") (pintype "passive"))
      (node (ref "C14") (pin "1") (pinfunction "1_1") (pintype "passive"))
      (node (ref "C15") (pin "1") (pinfunction "1_1") (pintype "passive"))
      (node (ref "C17") (pin "1") (pinfunction "1_1") (pintype "passive"))
      (node (ref "C18") (pin "1") (pinfunction "1_1") (pintype "passive"))
      (node (ref "C2") (pin "2") (pinfunction "2_2") (pintype "passive"))
      (node (ref "C21") (pin "1") (pinfunction "1_1") (pintype "passive"))
      (node (ref "C21") (pin "2") (pinfunction "2_2") (pintype "passive"))
      (node (ref "C21") (pin "3") (pinfunction "3_3") (pintype "passive"))
      (node (ref "C26") (pin "2") (pinfunction "2_2") (pintype "passive"))
      (node (ref "C27") (pin "2") (pinfunction "2_2") (pintype "passive"))
      (node (ref "C3") (pin "2") (pinfunction "2_2") (pintype "passive"))
      (node (ref "C4") (pin "2") (pinfunction "2_2") (pintype "passive"))
      (node (ref "C5") (pin "1") (pinfunction "1_1") (pintype "passive"))
      (node (ref "IC1") (pin "2") (pinfunction "G_2") (pintype "power_in"))
      (node (ref "IC2") (pin "2") (pinfunction "G_2") (pintype "power_in"))
      (node (ref "J3") (pin "1") (pinfunction "1_1") (pintype "passive"))
      (node (ref "LED2") (pin "2") (pinfunction "2_2") (pintype "passive"))
      (node (ref "U1") (pin "5") (pinfunction "GND_5") (pintype "power_in"))
      (node (ref "U3") (pin "5") (pinfunction "GND_5") (pintype "power_in"))
      (node (ref "U4") (pin "5") (pinfunction "GND_5") (pintype "power_in"))
      (node (ref "U6") (pin "5") (pinfunction "GND_5") (pintype "power_in"))
      (node (ref "U7") (pin "12") (pinfunction "VSS_12") (pintype "power_in"))
    )
    (net (code "45") (name "Net-(D4-K)") (class "Default")
      (node (ref "D4") (pin "2") (pinfunction "K_2") (pintype "passive"))
      (node (ref "R14") (pin "2") (pinfunction "2_2") (pintype "passive"))
      (node (ref "U7") (pin "27") (pinfunction "HO1_27") (pintype "output"))
    )
    (net (code "46") (name "Net-(D5-K)") (class "Default")
      (node (ref "D5") (pin "2") (pinfunction "K_2") (pintype "passive"))
      (node (ref "R15") (pin "2") (pinfunction "2_2") (pintype "passive"))
      (node (ref "U7") (pin "23") (pinfunction "HO2_23") (pintype "output"))
    )
    (net (code "47") (name "Net-(D6-K)") (class "Default")
      (node (ref "D6") (pin "2") (pinfunction "K_2") (pintype "passive"))
      (node (ref "R17") (pin "2") (pinfunction "2_2") (pintype "passive"))
      (node (ref "U7") (pin "19") (pinfunction "HO3_19") (pintype "output"))
    )
    (net (code "48") (name "Net-(D7-K)") (class "Default")
      (node (ref "D7") (pin "2") (pinfunction "K_2") (pintype "passive"))
      (node (ref "R19") (pin "2") (pinfunction "2_2") (pintype "passive"))
      (node (ref "U7") (pin "16") (pinfunction "LO1_16") (pintype "output"))
    )
    (net (code "49") (name "Net-(D8-K)") (class "Default")
      (node (ref "D8") (pin "2") (pinfunction "K_2") (pintype "passive"))
      (node (ref "R20") (pin "2") (pinfunction "2_2") (pintype "passive"))
      (node (ref "U7") (pin "15") (pinfunction "LO2_15") (pintype "output"))
    )
    (net (code "50") (name "Net-(D9-K)") (class "Default")
      (node (ref "D9") (pin "2") (pinfunction "K_2") (pintype "passive"))
      (node (ref "R21") (pin "2") (pinfunction "2_2") (pintype "passive"))
      (node (ref "U7") (pin "14") (pinfunction "LO3_14") (pintype "output"))
    )
    (net (code "51") (name "Net-(LED1-Pad1)") (class "Default")
      (node (ref "LED1") (pin "1") (pinfunction "1_1") (pintype "passive"))
      (node (ref "R3") (pin "2") (pinfunction "2_2") (pintype "passive"))
    )
    (net (code "52") (name "Net-(LED2-Pad1)") (class "Default")
      (node (ref "LED2") (pin "1") (pinfunction "1_1") (pintype "passive"))
      (node (ref "R6") (pin "2") (pinfunction "2_2") (pintype "passive"))
    )
    (net (code "53") (name "Net-(LED3-Pad2)") (class "Default")
      (node (ref "LED3") (pin "2") (pinfunction "2_2") (pintype "passive"))
      (node (ref "R13") (pin "1") (pinfunction "1_1") (pintype "passive"))
    )
    (net (code "54") (name "Net-(U5-A)") (class "Default")
      (node (ref "R8") (pin "1") (pinfunction "1_1") (pintype "passive"))
      (node (ref "U5") (pin "2") (pinfunction "A_2") (pintype "bidirectional"))
    )
    (net (code "55") (name "Net-(U7-COM)") (class "Default")
      (node (ref "C28") (pin "1") (pinfunction "1_1") (pintype "passive"))
      (node (ref "R22") (pin "2") (pinfunction "2_2") (pintype "passive"))
      (node (ref "U7") (pin "13") (pinfunction "COM_13") (pintype "power_in"))
    )
    (net (code "56") (name "Net-(U7-ITRIP)") (class "Default")
      (node (ref "C27") (pin "1") (pinfunction "1_1") (pintype "passive"))
      (node (ref "R18") (pin "2") (pinfunction "2_2") (pintype "passive"))
      (node (ref "U7") (pin "9") (pinfunction "ITRIP_9") (pintype "input"))
    )
    (net (code "57") (name "Vin") (class "Default")
      (node (ref "C1") (pin "1") (pinfunction "1_1") (pintype "passive"))
      (node (ref "C2") (pin "1") (pinfunction "1_1") (pintype "passive"))
      (node (ref "IC1") (pin "1") (pinfunction "I_1") (pintype "power_in"))
      (node (ref "J3") (pin "2") (pinfunction "2_2") (pintype "passive"))
    )
    (net (code "58") (name "Vin VDK") (class "Default")
      (node (ref "C9") (pin "1") (pinfunction "1_1") (pintype "passive"))
      (node (ref "J1") (pin "3") (pinfunction "3_3") (pintype "passive"))
      (node (ref "J2") (pin "2") (pinfunction "2_2") (pintype "passive"))
      (node (ref "J4") (pin "1") (pinfunction "1_1") (pintype "passive"))
      (node (ref "U2") (pin "3") (pinfunction "IN_3") (pintype "passive"))
    )
    (net (code "59") (name "unconnected-(*1-5V-Pad38)") (class "Default")
      (node (ref "*1") (pin "38") (pinfunction "5V_38") (pintype "power_in"))
    )
    (net (code "60") (name "unconnected-(*1-A0-Pad6)") (class "Default")
      (node (ref "*1") (pin "6") (pinfunction "A0_6") (pintype "bidirectional"))
    )
    (net (code "61") (name "unconnected-(*1-A1-Pad7)") (class "Default")
      (node (ref "*1") (pin "7") (pinfunction "A1_7") (pintype "bidirectional"))
    )
    (net (code "62") (name "unconnected-(*1-A4-Pad10)") (class "Default")
      (node (ref "*1") (pin "10") (pinfunction "A4_10") (pintype "bidirectional"))
    )
    (net (code "63") (name "unconnected-(*1-A5-Pad11)") (class "Default")
      (node (ref "*1") (pin "11") (pinfunction "A5_11") (pintype "bidirectional"))
    )
    (net (code "64") (name "unconnected-(*1-A6-Pad12)") (class "Default")
      (node (ref "*1") (pin "12") (pinfunction "A6_12") (pintype "bidirectional"))
    )
    (net (code "65") (name "unconnected-(*1-A11-Pad28)") (class "Default")
      (node (ref "*1") (pin "28") (pinfunction "A11_28") (pintype "bidirectional"))
    )
    (net (code "66") (name "unconnected-(*1-A12-Pad29)") (class "Default")
      (node (ref "*1") (pin "29") (pinfunction "A12_29") (pintype "bidirectional"))
    )
    (net (code "67") (name "unconnected-(*1-A15-Pad30)") (class "Default")
      (node (ref "*1") (pin "30") (pinfunction "A15_30") (pintype "bidirectional"))
    )
    (net (code "68") (name "unconnected-(*1-B3-Pad31)") (class "Default")
      (node (ref "*1") (pin "31") (pinfunction "B3_31") (pintype "bidirectional"))
    )
    (net (code "69") (name "unconnected-(*1-B4-Pad32)") (class "Default")
      (node (ref "*1") (pin "32") (pinfunction "B4_32") (pintype "bidirectional"))
    )
    (net (code "70") (name "unconnected-(*1-B5-Pad33)") (class "Default")
      (node (ref "*1") (pin "33") (pinfunction "B5_33") (pintype "bidirectional"))
    )
    (net (code "71") (name "unconnected-(*1-B6-Pad34)") (class "Default")
      (node (ref "*1") (pin "34") (pinfunction "B6_34") (pintype "bidirectional"))
    )
    (net (code "72") (name "unconnected-(*1-B7-Pad35)") (class "Default")
      (node (ref "*1") (pin "35") (pinfunction "B7_35") (pintype "bidirectional"))
    )
    (net (code "73") (name "unconnected-(*1-B10-Pad17)") (class "Default")
      (node (ref "*1") (pin "17") (pinfunction "B10_17") (pintype "bidirectional"))
    )
    (net (code "74") (name "unconnected-(*1-B12-Pad21)") (class "Default")
      (node (ref "*1") (pin "21") (pinfunction "B12_21") (pintype "bidirectional"))
    )
    (net (code "75") (name "unconnected-(*1-B13-Pad22)") (class "Default")
      (node (ref "*1") (pin "22") (pinfunction "B13_22") (pintype "bidirectional"))
    )
    (net (code "76") (name "unconnected-(*1-B14-Pad23)") (class "Default")
      (node (ref "*1") (pin "23") (pinfunction "B14_23") (pintype "bidirectional"))
    )
    (net (code "77") (name "unconnected-(*1-B15-Pad24)") (class "Default")
      (node (ref "*1") (pin "24") (pinfunction "B15_24") (pintype "bidirectional"))
    )
    (net (code "78") (name "unconnected-(*1-C13-Pad2)") (class "Default")
      (node (ref "*1") (pin "2") (pinfunction "C13_2") (pintype "bidirectional"))
    )
    (net (code "79") (name "unconnected-(*1-C14-Pad3)") (class "Default")
      (node (ref "*1") (pin "3") (pinfunction "C14_3") (pintype "bidirectional"))
    )
    (net (code "80") (name "unconnected-(*1-C15-Pad4)") (class "Default")
      (node (ref "*1") (pin "4") (pinfunction "C15_4") (pintype "bidirectional"))
    )
    (net (code "81") (name "unconnected-(*1-RST-Pad5)") (class "Default")
      (node (ref "*1") (pin "5") (pinfunction "RST_5") (pintype "power_in"))
    )
    (net (code "82") (name "unconnected-(*1-VBAT-Pad1)") (class "Default")
      (node (ref "*1") (pin "1") (pinfunction "VBAT_1") (pintype "power_in"))
    )
    (net (code "83") (name "unconnected-(U7-NC-Pad17)") (class "Default")
      (node (ref "U7") (pin "17") (pinfunction "NC_17") (pintype "passive+no_connect"))
    )
    (net (code "84") (name "unconnected-(U7-NC-Pad21)") (class "Default")
      (node (ref "U7") (pin "21") (pinfunction "NC_21") (pintype "passive+no_connect"))
    )
    (net (code "85") (name "unconnected-(U7-NC-Pad25)") (class "Default")
      (node (ref "U7") (pin "25") (pinfunction "NC_25") (pintype "passive+no_connect"))
    )
  )
)
